# stepdown-richtig.net
KiCad netlist of a schematic drawn in EAGLE
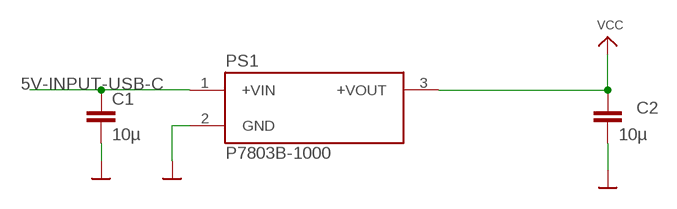
[diagram p0: schematic, sheet 1]

(export (version "E")
  (design (tool "Eeschema 10.0.6"))
  (components
    (comp (ref "C1")
      (value "10µ")
      (footprint "eagle-import:C1206")
      (libsource (lib "eagle-import") (part "C-EUC1206"))
    )
    (comp (ref "C2")
      (value "10µ")
      (footprint "eagle-import:C1206")
      (libsource (lib "eagle-import") (part "C-EUC1206"))
    )
    (comp (ref "PS1")
      (value "P7803B-1000")
      (footprint "eagle-import:CONV_P7803B-1000")
      (fields (field (name "MF") "CUI"))
      (libsource (lib "eagle-import") (part "P7803B-1000"))
    )
  )
  (nets
    (net (code "1") (name "/5V-INPUT-USB-C") (class "Default")
      (node (ref "C1") (pin "1") (pinfunction "1_1") (pintype "passive"))
      (node (ref "PS1") (pin "1") (pinfunction "+VIN_1") (pintype "input"))
    )
    (net (code "2") (name "GND") (class "Default")
      (node (ref "C1") (pin "2") (pinfunction "2_2") (pintype "passive"))
      (node (ref "C2") (pin "2") (pinfunction "2_2") (pintype "passive"))
      (node (ref "PS1") (pin "2") (pinfunction "GND_2") (pintype "power_in"))
    )
    (net (code "3") (name "VCC") (class "Default")
      (node (ref "C2") (pin "1") (pinfunction "1_1") (pintype "passive"))
      (node (ref "PS1") (pin "3") (pinfunction "+VOUT_3") (pintype "output"))
    )
  )
)
